# c4-tracker.net
KiCad netlist of a schematic drawn in EAGLE
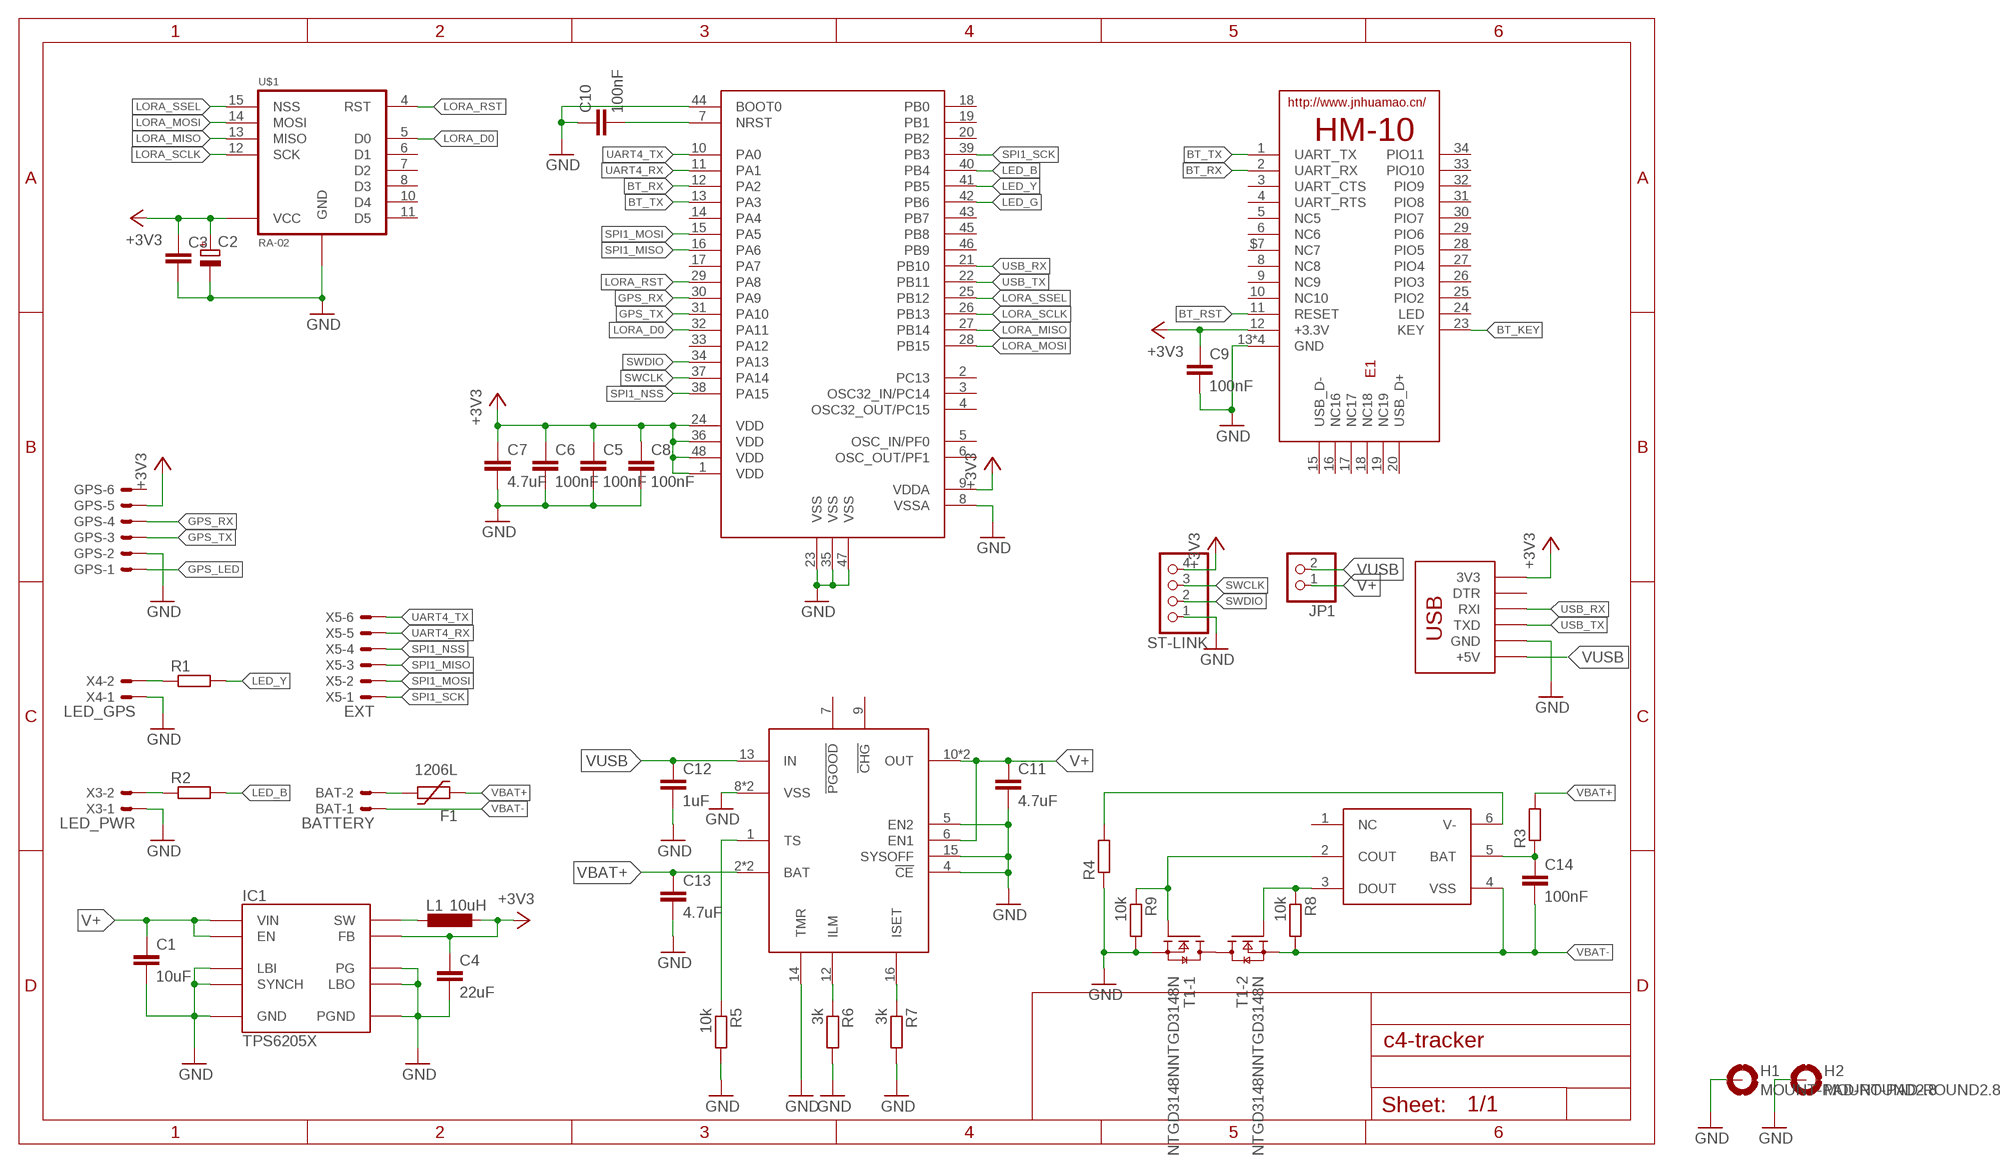
[diagram p0: schematic, sheet 1]

(export (version "E")
  (design (tool "Eeschema 10.0.6"))
  (components
    (comp (ref "BAT")
      (value "BATTERY")
      (footprint "eagle-import:53261-02")
      (libsource (lib "eagle-import") (part "53?-02261"))
    )
    (comp (ref "C1")
      (value "10uF")
      (footprint "eagle-import:C0805")
      (libsource (lib "eagle-import") (part "C-EUC0805"))
    )
    (comp (ref "C2")
      (value "CPOL-EUC")
      (footprint "eagle-import:PANASONIC_C")
      (libsource (lib "eagle-import") (part "CPOL-EUC"))
    )
    (comp (ref "C3")
      (value "C-EUC0805")
      (footprint "eagle-import:C0805")
      (libsource (lib "eagle-import") (part "C-EUC0805"))
    )
    (comp (ref "C4")
      (value "22uF")
      (footprint "eagle-import:C0805")
      (libsource (lib "eagle-import") (part "C-EUC0805"))
    )
    (comp (ref "C5")
      (value "100nF")
      (footprint "eagle-import:C0805")
      (libsource (lib "eagle-import") (part "C-EUC0805"))
    )
    (comp (ref "C6")
      (value "100nF")
      (footprint "eagle-import:C0805")
      (libsource (lib "eagle-import") (part "C-EUC0805"))
    )
    (comp (ref "C7")
      (value "4.7uF")
      (footprint "eagle-import:C0805")
      (libsource (lib "eagle-import") (part "C-EUC0805"))
    )
    (comp (ref "C8")
      (value "100nF")
      (footprint "eagle-import:C0805")
      (libsource (lib "eagle-import") (part "C-EUC0805"))
    )
    (comp (ref "C9")
      (value "100nF")
      (footprint "eagle-import:C0805")
      (libsource (lib "eagle-import") (part "C-EUC0805"))
    )
    (comp (ref "C10")
      (value "100nF")
      (footprint "eagle-import:C0805")
      (libsource (lib "eagle-import") (part "C-EUC0805"))
    )
    (comp (ref "C11")
      (value "4.7uF")
      (footprint "eagle-import:C0805")
      (libsource (lib "eagle-import") (part "C-EUC0805"))
    )
    (comp (ref "C12")
      (value "1uF")
      (footprint "eagle-import:C0805")
      (libsource (lib "eagle-import") (part "C-EUC0805"))
    )
    (comp (ref "C13")
      (value "4.7uF")
      (footprint "eagle-import:C0805")
      (libsource (lib "eagle-import") (part "C-EUC0805"))
    )
    (comp (ref "C14")
      (value "100nF")
      (footprint "eagle-import:C0805")
      (libsource (lib "eagle-import") (part "C-EUC0805"))
    )
    (comp (ref "E1")
      (value "HM-10-BOARD")
      (footprint "eagle-import:26.9X13X2.2_BOARD")
      (libsource (lib "eagle-import") (part "HM-10-BOARD"))
    )
    (comp (ref "F1")
      (value "1206L")
      (footprint "eagle-import:1206L")
      (libsource (lib "eagle-import") (part "1206L"))
    )
    (comp (ref "GPS")
      (value "53398-06")
      (footprint "eagle-import:53398-06")
      (libsource (lib "eagle-import") (part "53?-06398"))
    )
    (comp (ref "H1")
      (value "MOUNT-PAD-ROUND2.8")
      (footprint "eagle-import:2,8-PAD")
      (libsource (lib "eagle-import") (part "MOUNT-PAD-ROUND2.8"))
    )
    (comp (ref "H2")
      (value "MOUNT-PAD-ROUND2.8")
      (footprint "eagle-import:2,8-PAD")
      (libsource (lib "eagle-import") (part "MOUNT-PAD-ROUND2.8"))
    )
    (comp (ref "IC1")
      (value "TPS6205X")
      (footprint "eagle-import:VSSOP10")
      (libsource (lib "eagle-import") (part "TPS6205X"))
    )
    (comp (ref "IC2")
      (value "BQ24075/9T")
      (footprint "eagle-import:VQFN16")
      (libsource (lib "eagle-import") (part "BQ24075/9T"))
    )
    (comp (ref "JP1")
      (value "PINHD-1X2")
      (footprint "eagle-import:1X02")
      (libsource (lib "eagle-import") (part "PINHD-1X2"))
    )
    (comp (ref "L1")
      (value "10uH")
      (footprint "eagle-import:CDRH5D28R")
      (libsource (lib "eagle-import") (part "CDRH5D28R"))
    )
    (comp (ref "MC1")
      (value "STM32F030CC-48")
      (footprint "eagle-import:LQFP48-7X7")
      (libsource (lib "eagle-import") (part "STM32F030CC-48"))
    )
    (comp (ref "R1")
      (value "R-EU_R0805")
      (footprint "eagle-import:R0805")
      (libsource (lib "eagle-import") (part "R-EU_R0805"))
    )
    (comp (ref "R2")
      (value "R-EU_R0805")
      (footprint "eagle-import:R0805")
      (libsource (lib "eagle-import") (part "R-EU_R0805"))
    )
    (comp (ref "R3")
      (value "R-EU_R0805")
      (footprint "eagle-import:R0805")
      (libsource (lib "eagle-import") (part "R-EU_R0805"))
    )
    (comp (ref "R4")
      (value "R-EU_R0805")
      (footprint "eagle-import:R0805")
      (libsource (lib "eagle-import") (part "R-EU_R0805"))
    )
    (comp (ref "R5")
      (value "10k")
      (footprint "eagle-import:R0805")
      (libsource (lib "eagle-import") (part "R-EU_R0805"))
    )
    (comp (ref "R6")
      (value "3k")
      (footprint "eagle-import:R0805")
      (libsource (lib "eagle-import") (part "R-EU_R0805"))
    )
    (comp (ref "R7")
      (value "3k")
      (footprint "eagle-import:R0805")
      (libsource (lib "eagle-import") (part "R-EU_R0805"))
    )
    (comp (ref "R8")
      (value "10k")
      (footprint "eagle-import:R0805")
      (libsource (lib "eagle-import") (part "R-EU_R0805"))
    )
    (comp (ref "R9")
      (value "10k")
      (footprint "eagle-import:R0805")
      (libsource (lib "eagle-import") (part "R-EU_R0805"))
    )
    (comp (ref "ST-LINK")
      (value "PINHD-1X4")
      (footprint "eagle-import:1X04")
      (libsource (lib "eagle-import") (part "PINHD-1X4"))
    )
    (comp (ref "T1")
      (value "NTGD3148NNTGD3148N")
      (footprint "eagle-import:TSOP-6")
      (libsource (lib "eagle-import") (part "NTGD3148NNTGD3148N"))
    )
    (comp (ref "U$1")
      (value "RA-02")
      (footprint "eagle-import:RA-01_RA-02")
      (libsource (lib "eagle-import") (part "RA-02"))
    )
    (comp (ref "U$2")
      (value "RS232_USB")
      (footprint "eagle-import:CP2102_MICRO_USB_BOARD")
      (libsource (lib "eagle-import") (part "RS232_USB"))
    )
    (comp (ref "U$3")
      (value "BQ2970")
      (footprint "eagle-import:WSON6")
      (libsource (lib "eagle-import") (part "BQ2970"))
    )
    (comp (ref "X3")
      (value "LED_PWR")
      (footprint "eagle-import:53261-02")
      (libsource (lib "eagle-import") (part "53?-02261"))
    )
    (comp (ref "X4")
      (value "LED_GPS")
      (footprint "eagle-import:53261-02")
      (libsource (lib "eagle-import") (part "53?-02261"))
    )
    (comp (ref "X5")
      (value "EXT")
      (footprint "eagle-import:53261-06")
      (libsource (lib "eagle-import") (part "53?-06261"))
    )
  )
  (nets
    (net (code "1") (name "+3V3") (class "Default")
      (node (ref "C2") (pin "+") (pinfunction "+_+") (pintype "passive"))
      (node (ref "C3") (pin "1") (pinfunction "1_1") (pintype "passive"))
      (node (ref "C4") (pin "1") (pinfunction "1_1") (pintype "passive"))
      (node (ref "C5") (pin "1") (pinfunction "1_1") (pintype "passive"))
      (node (ref "C6") (pin "1") (pinfunction "1_1") (pintype "passive"))
      (node (ref "C7") (pin "1") (pinfunction "1_1") (pintype "passive"))
      (node (ref "C8") (pin "1") (pinfunction "1_1") (pintype "passive"))
      (node (ref "C9") (pin "1") (pinfunction "1_1") (pintype "passive"))
      (node (ref "E1") (pin "12") (pinfunction "+3.3V_12") (pintype "bidirectional"))
      (node (ref "GPS") (pin "5") (pinfunction "S_5") (pintype "passive"))
      (node (ref "IC1") (pin "P$5") (pinfunction "FB_P$5") (pintype "bidirectional"))
      (node (ref "L1") (pin "1") (pinfunction "1_1") (pintype "passive"))
      (node (ref "MC1") (pin "1") (pinfunction "VDD_1") (pintype "bidirectional"))
      (node (ref "MC1") (pin "24") (pinfunction "VDD_24") (pintype "bidirectional"))
      (node (ref "MC1") (pin "36") (pinfunction "VDD_36") (pintype "bidirectional"))
      (node (ref "MC1") (pin "48") (pinfunction "VDD_48") (pintype "bidirectional"))
      (node (ref "MC1") (pin "9") (pinfunction "VDDA_9") (pintype "bidirectional"))
      (node (ref "ST-LINK") (pin "4") (pinfunction "4_4") (pintype "passive"))
      (node (ref "U$1") (pin "3") (pinfunction "VCC_3") (pintype "power_in"))
      (node (ref "U$2") (pin "3V3") (pinfunction "3V3_3V3") (pintype "power_in"))
    )
    (net (code "2") (name "BT_KEY") (class "Default")
      (node (ref "E1") (pin "23") (pinfunction "KEY_23") (pintype "bidirectional"))
    )
    (net (code "3") (name "BT_RST") (class "Default")
      (node (ref "E1") (pin "11") (pinfunction "RESET_11") (pintype "bidirectional"))
    )
    (net (code "4") (name "BT_RX") (class "Default")
      (node (ref "E1") (pin "2") (pinfunction "UART_RX_2") (pintype "bidirectional"))
      (node (ref "MC1") (pin "12") (pinfunction "PA2_12") (pintype "bidirectional"))
    )
    (net (code "5") (name "BT_TX") (class "Default")
      (node (ref "E1") (pin "1") (pinfunction "UART_TX_1") (pintype "bidirectional"))
      (node (ref "MC1") (pin "13") (pinfunction "PA3_13") (pintype "bidirectional"))
    )
    (net (code "6") (name "GND") (class "Default")
      (node (ref "C1") (pin "2") (pinfunction "2_2") (pintype "passive"))
      (node (ref "C10") (pin "1") (pinfunction "1_1") (pintype "passive"))
      (node (ref "C11") (pin "2") (pinfunction "2_2") (pintype "passive"))
      (node (ref "C12") (pin "2") (pinfunction "2_2") (pintype "passive"))
      (node (ref "C13") (pin "2") (pinfunction "2_2") (pintype "passive"))
      (node (ref "C2") (pin "-") (pinfunction "-_-") (pintype "passive"))
      (node (ref "C3") (pin "2") (pinfunction "2_2") (pintype "passive"))
      (node (ref "C4") (pin "2") (pinfunction "2_2") (pintype "passive"))
      (node (ref "C5") (pin "2") (pinfunction "2_2") (pintype "passive"))
      (node (ref "C6") (pin "2") (pinfunction "2_2") (pintype "passive"))
      (node (ref "C7") (pin "2") (pinfunction "2_2") (pintype "passive"))
      (node (ref "C8") (pin "2") (pinfunction "2_2") (pintype "passive"))
      (node (ref "C9") (pin "2") (pinfunction "2_2") (pintype "passive"))
      (node (ref "E1") (pin "13") (pinfunction "GND_13") (pintype "bidirectional"))
      (node (ref "E1") (pin "14") (pinfunction "GND_14") (pintype "bidirectional"))
      (node (ref "E1") (pin "21") (pinfunction "GND_21") (pintype "bidirectional"))
      (node (ref "E1") (pin "22") (pinfunction "GND_22") (pintype "bidirectional"))
      (node (ref "GPS") (pin "2") (pinfunction "S_2") (pintype "passive"))
      (node (ref "H1") (pin "B2,8") (pinfunction "MOUNT_B2,8") (pintype "passive"))
      (node (ref "H2") (pin "B2,8") (pinfunction "MOUNT_B2,8") (pintype "passive"))
      (node (ref "IC1") (pin "P$10") (pinfunction "PGND_P$10") (pintype "bidirectional"))
      (node (ref "IC1") (pin "P$2") (pinfunction "LBO_P$2") (pintype "bidirectional"))
      (node (ref "IC1") (pin "P$3") (pinfunction "GND_P$3") (pintype "power_in"))
      (node (ref "IC1") (pin "P$4") (pinfunction "PG_P$4") (pintype "bidirectional"))
      (node (ref "IC1") (pin "P$6") (pinfunction "LBI_P$6") (pintype "bidirectional"))
      (node (ref "IC1") (pin "P$7") (pinfunction "SYNCH_P$7") (pintype "bidirectional"))
      (node (ref "IC2") (pin "14") (pinfunction "TMR_14") (pintype "bidirectional"))
      (node (ref "IC2") (pin "15") (pinfunction "SYSOFF_15") (pintype "bidirectional"))
      (node (ref "IC2") (pin "17") (pinfunction "VSS_17") (pintype "bidirectional"))
      (node (ref "IC2") (pin "4") (pinfunction "~{CE}_4") (pintype "bidirectional"))
      (node (ref "IC2") (pin "5") (pinfunction "EN2_5") (pintype "bidirectional"))
      (node (ref "IC2") (pin "8") (pinfunction "VSS_8") (pintype "bidirectional"))
      (node (ref "MC1") (pin "23") (pinfunction "VSS_23") (pintype "bidirectional"))
      (node (ref "MC1") (pin "35") (pinfunction "VSS_35") (pintype "bidirectional"))
      (node (ref "MC1") (pin "44") (pinfunction "BOOT0_44") (pintype "bidirectional"))
      (node (ref "MC1") (pin "47") (pinfunction "VSS_47") (pintype "bidirectional"))
      (node (ref "MC1") (pin "8") (pinfunction "VSSA_8") (pintype "bidirectional"))
      (node (ref "R4") (pin "1") (pinfunction "1_1") (pintype "passive"))
      (node (ref "R5") (pin "2") (pinfunction "2_2") (pintype "passive"))
      (node (ref "R6") (pin "2") (pinfunction "2_2") (pintype "passive"))
      (node (ref "R7") (pin "2") (pinfunction "2_2") (pintype "passive"))
      (node (ref "R9") (pin "2") (pinfunction "2_2") (pintype "passive"))
      (node (ref "ST-LINK") (pin "1") (pinfunction "1_1") (pintype "passive"))
      (node (ref "T1") (pin "5") (pinfunction "S_5") (pintype "passive"))
      (node (ref "U$1") (pin "1") (pinfunction "GND_1") (pintype "power_in"))
      (node (ref "U$1") (pin "16") (pinfunction "GND_16") (pintype "power_in"))
      (node (ref "U$1") (pin "2") (pinfunction "GND_2") (pintype "power_in"))
      (node (ref "U$1") (pin "9") (pinfunction "GND_9") (pintype "power_in"))
      (node (ref "U$2") (pin "GND") (pinfunction "GND_GND") (pintype "power_in"))
      (node (ref "X3") (pin "1") (pinfunction "S_1") (pintype "passive"))
      (node (ref "X4") (pin "1") (pinfunction "S_1") (pintype "passive"))
    )
    (net (code "7") (name "GPS_LED") (class "Default")
      (node (ref "GPS") (pin "1") (pinfunction "S_1") (pintype "passive"))
    )
    (net (code "8") (name "GPS_RX") (class "Default")
      (node (ref "GPS") (pin "4") (pinfunction "S_4") (pintype "passive"))
      (node (ref "MC1") (pin "30") (pinfunction "PA9_30") (pintype "bidirectional"))
    )
    (net (code "9") (name "GPS_TX") (class "Default")
      (node (ref "GPS") (pin "3") (pinfunction "S_3") (pintype "passive"))
      (node (ref "MC1") (pin "31") (pinfunction "PA10_31") (pintype "bidirectional"))
    )
    (net (code "10") (name "LED_B") (class "Default")
      (node (ref "MC1") (pin "40") (pinfunction "PB4_40") (pintype "bidirectional"))
      (node (ref "R2") (pin "2") (pinfunction "2_2") (pintype "passive"))
    )
    (net (code "11") (name "LED_G") (class "Default")
      (node (ref "MC1") (pin "42") (pinfunction "PB6_42") (pintype "bidirectional"))
    )
    (net (code "12") (name "LED_Y") (class "Default")
      (node (ref "MC1") (pin "41") (pinfunction "PB5_41") (pintype "bidirectional"))
      (node (ref "R1") (pin "2") (pinfunction "2_2") (pintype "passive"))
    )
    (net (code "13") (name "LORA_D0") (class "Default")
      (node (ref "MC1") (pin "32") (pinfunction "PA11_32") (pintype "bidirectional"))
      (node (ref "U$1") (pin "5") (pinfunction "D0_5") (pintype "bidirectional"))
    )
    (net (code "14") (name "LORA_MISO") (class "Default")
      (node (ref "MC1") (pin "27") (pinfunction "PB14_27") (pintype "bidirectional"))
      (node (ref "U$1") (pin "13") (pinfunction "MISO_13") (pintype "bidirectional"))
    )
    (net (code "15") (name "LORA_MOSI") (class "Default")
      (node (ref "MC1") (pin "28") (pinfunction "PB15_28") (pintype "bidirectional"))
      (node (ref "U$1") (pin "14") (pinfunction "MOSI_14") (pintype "bidirectional"))
    )
    (net (code "16") (name "LORA_RST") (class "Default")
      (node (ref "MC1") (pin "29") (pinfunction "PA8_29") (pintype "bidirectional"))
      (node (ref "U$1") (pin "4") (pinfunction "RST_4") (pintype "bidirectional"))
    )
    (net (code "17") (name "LORA_SCLK") (class "Default")
      (node (ref "MC1") (pin "26") (pinfunction "PB13_26") (pintype "bidirectional"))
      (node (ref "U$1") (pin "12") (pinfunction "SCK_12") (pintype "bidirectional"))
    )
    (net (code "18") (name "LORA_SSEL") (class "Default")
      (node (ref "MC1") (pin "25") (pinfunction "PB12_25") (pintype "bidirectional"))
      (node (ref "U$1") (pin "15") (pinfunction "NSS_15") (pintype "bidirectional"))
    )
    (net (code "19") (name "Net-(BATB-S)") (class "Default")
      (node (ref "BAT") (pin "2") (pinfunction "S_2") (pintype "passive"))
      (node (ref "F1") (pin "P$2") (pinfunction "2_P$2") (pintype "passive"))
    )
    (net (code "20") (name "Net-(IC1-SW)") (class "Default")
      (node (ref "IC1") (pin "P$9") (pinfunction "SW_P$9") (pintype "bidirectional"))
      (node (ref "L1") (pin "2") (pinfunction "2_2") (pintype "passive"))
    )
    (net (code "21") (name "Net-(IC2-ILM)") (class "Default")
      (node (ref "IC2") (pin "12") (pinfunction "ILM_12") (pintype "bidirectional"))
      (node (ref "R6") (pin "1") (pinfunction "1_1") (pintype "passive"))
    )
    (net (code "22") (name "Net-(IC2-ISET)") (class "Default")
      (node (ref "IC2") (pin "16") (pinfunction "ISET_16") (pintype "bidirectional"))
      (node (ref "R7") (pin "1") (pinfunction "1_1") (pintype "passive"))
    )
    (net (code "23") (name "Net-(IC2-TS)") (class "Default")
      (node (ref "IC2") (pin "1") (pinfunction "TS_1") (pintype "bidirectional"))
      (node (ref "R5") (pin "1") (pinfunction "1_1") (pintype "passive"))
    )
    (net (code "24") (name "Net-(MC1-NRST)") (class "Default")
      (node (ref "C10") (pin "2") (pinfunction "2_2") (pintype "passive"))
      (node (ref "MC1") (pin "7") (pinfunction "NRST_7") (pintype "bidirectional"))
    )
    (net (code "25") (name "Net-(T1A-D)") (class "Default")
      (node (ref "T1") (pin "4") (pinfunction "D_4") (pintype "passive"))
      (node (ref "T1") (pin "6") (pinfunction "D_6") (pintype "passive"))
    )
    (net (code "26") (name "Net-(T1A-G)") (class "Default")
      (node (ref "R9") (pin "1") (pinfunction "1_1") (pintype "passive"))
      (node (ref "T1") (pin "1") (pinfunction "G_1") (pintype "passive"))
      (node (ref "U$3") (pin "2") (pinfunction "COUT_2") (pintype "bidirectional"))
    )
    (net (code "27") (name "Net-(T1B-G)") (class "Default")
      (node (ref "R8") (pin "1") (pinfunction "1_1") (pintype "passive"))
      (node (ref "T1") (pin "3") (pinfunction "G_3") (pintype "passive"))
      (node (ref "U$3") (pin "3") (pinfunction "DOUT_3") (pintype "bidirectional"))
    )
    (net (code "28") (name "Net-(U$3-BAT)") (class "Default")
      (node (ref "C14") (pin "1") (pinfunction "1_1") (pintype "passive"))
      (node (ref "R3") (pin "1") (pinfunction "1_1") (pintype "passive"))
      (node (ref "U$3") (pin "5") (pinfunction "BAT_5") (pintype "bidirectional"))
    )
    (net (code "29") (name "Net-(U$3-V-)") (class "Default")
      (node (ref "R4") (pin "2") (pinfunction "2_2") (pintype "passive"))
      (node (ref "U$3") (pin "6") (pinfunction "V-_6") (pintype "bidirectional"))
    )
    (net (code "30") (name "Net-(X3B-S)") (class "Default")
      (node (ref "R2") (pin "1") (pinfunction "1_1") (pintype "passive"))
      (node (ref "X3") (pin "2") (pinfunction "S_2") (pintype "passive"))
    )
    (net (code "31") (name "Net-(X4B-S)") (class "Default")
      (node (ref "R1") (pin "1") (pinfunction "1_1") (pintype "passive"))
      (node (ref "X4") (pin "2") (pinfunction "S_2") (pintype "passive"))
    )
    (net (code "32") (name "SPI1_MISO") (class "Default")
      (node (ref "MC1") (pin "16") (pinfunction "PA6_16") (pintype "bidirectional"))
      (node (ref "X5") (pin "3") (pinfunction "S_3") (pintype "passive"))
    )
    (net (code "33") (name "SPI1_MOSI") (class "Default")
      (node (ref "MC1") (pin "15") (pinfunction "PA5_15") (pintype "bidirectional"))
      (node (ref "X5") (pin "2") (pinfunction "S_2") (pintype "passive"))
    )
    (net (code "34") (name "SPI1_NSS") (class "Default")
      (node (ref "MC1") (pin "38") (pinfunction "PA15_38") (pintype "bidirectional"))
      (node (ref "X5") (pin "4") (pinfunction "S_4") (pintype "passive"))
    )
    (net (code "35") (name "SPI1_SCK") (class "Default")
      (node (ref "MC1") (pin "39") (pinfunction "PB3_39") (pintype "bidirectional"))
      (node (ref "X5") (pin "1") (pinfunction "S_1") (pintype "passive"))
    )
    (net (code "36") (name "SWCLK") (class "Default")
      (node (ref "MC1") (pin "37") (pinfunction "PA14_37") (pintype "bidirectional"))
      (node (ref "ST-LINK") (pin "3") (pinfunction "3_3") (pintype "passive"))
    )
    (net (code "37") (name "SWDIO") (class "Default")
      (node (ref "MC1") (pin "34") (pinfunction "PA13_34") (pintype "bidirectional"))
      (node (ref "ST-LINK") (pin "2") (pinfunction "2_2") (pintype "passive"))
    )
    (net (code "38") (name "UART4_RX") (class "Default")
      (node (ref "MC1") (pin "11") (pinfunction "PA1_11") (pintype "bidirectional"))
      (node (ref "X5") (pin "5") (pinfunction "S_5") (pintype "passive"))
    )
    (net (code "39") (name "UART4_TX") (class "Default")
      (node (ref "MC1") (pin "10") (pinfunction "PA0_10") (pintype "bidirectional"))
      (node (ref "X5") (pin "6") (pinfunction "S_6") (pintype "passive"))
    )
    (net (code "40") (name "USB_RX") (class "Default")
      (node (ref "MC1") (pin "21") (pinfunction "PB10_21") (pintype "bidirectional"))
      (node (ref "U$2") (pin "RXI") (pinfunction "RXI_RXI") (pintype "input"))
    )
    (net (code "41") (name "USB_TX") (class "Default")
      (node (ref "MC1") (pin "22") (pinfunction "PB11_22") (pintype "bidirectional"))
      (node (ref "U$2") (pin "TXD") (pinfunction "TXD_TXD") (pintype "output"))
    )
    (net (code "42") (name "V+") (class "Default")
      (node (ref "C1") (pin "1") (pinfunction "1_1") (pintype "passive"))
      (node (ref "C11") (pin "1") (pinfunction "1_1") (pintype "passive"))
      (node (ref "IC1") (pin "P$1") (pinfunction "VIN_P$1") (pintype "power_in"))
      (node (ref "IC1") (pin "P$8") (pinfunction "EN_P$8") (pintype "input"))
      (node (ref "IC2") (pin "10") (pinfunction "OUT_10") (pintype "bidirectional"))
      (node (ref "IC2") (pin "11") (pinfunction "OUT_11") (pintype "bidirectional"))
      (node (ref "IC2") (pin "6") (pinfunction "EN1_6") (pintype "bidirectional"))
      (node (ref "JP1") (pin "1") (pinfunction "1_1") (pintype "passive"))
    )
    (net (code "43") (name "VBAT+") (class "Default")
      (node (ref "C13") (pin "1") (pinfunction "1_1") (pintype "passive"))
      (node (ref "F1") (pin "P$1") (pinfunction "1_P$1") (pintype "passive"))
      (node (ref "IC2") (pin "2") (pinfunction "BAT_2") (pintype "bidirectional"))
      (node (ref "IC2") (pin "3") (pinfunction "BAT_3") (pintype "bidirectional"))
      (node (ref "R3") (pin "2") (pinfunction "2_2") (pintype "passive"))
    )
    (net (code "44") (name "VBAT-") (class "Default")
      (node (ref "BAT") (pin "1") (pinfunction "S_1") (pintype "passive"))
      (node (ref "C14") (pin "2") (pinfunction "2_2") (pintype "passive"))
      (node (ref "R8") (pin "2") (pinfunction "2_2") (pintype "passive"))
      (node (ref "T1") (pin "2") (pinfunction "S_2") (pintype "passive"))
      (node (ref "U$3") (pin "4") (pinfunction "VSS_4") (pintype "bidirectional"))
    )
    (net (code "45") (name "VUSB") (class "Default")
      (node (ref "C12") (pin "1") (pinfunction "1_1") (pintype "passive"))
      (node (ref "IC2") (pin "13") (pinfunction "IN_13") (pintype "bidirectional"))
      (node (ref "JP1") (pin "2") (pinfunction "2_2") (pintype "passive"))
      (node (ref "U$2") (pin "+5V") (pinfunction "+5V_+5V") (pintype "power_in"))
    )
    (net (code "46") (name "unconnected-(E1-LED-Pad24)") (class "Default")
      (node (ref "E1") (pin "24") (pinfunction "LED_24") (pintype "bidirectional"))
    )
    (net (code "47") (name "unconnected-(E1-NC5-Pad5)") (class "Default")
      (node (ref "E1") (pin "5") (pinfunction "NC5_5") (pintype "bidirectional"))
    )
    (net (code "48") (name "unconnected-(E1-NC6-Pad6)") (class "Default")
      (node (ref "E1") (pin "6") (pinfunction "NC6_6") (pintype "bidirectional"))
    )
    (net (code "49") (name "unconnected-(E1-NC7-Pad$7)") (class "Default")
      (node (ref "E1") (pin "$7") (pinfunction "NC7_$7") (pintype "bidirectional"))
    )
    (net (code "50") (name "unconnected-(E1-NC8-Pad8)") (class "Default")
      (node (ref "E1") (pin "8") (pinfunction "NC8_8") (pintype "bidirectional"))
    )
    (net (code "51") (name "unconnected-(E1-NC9-Pad9)") (class "Default")
      (node (ref "E1") (pin "9") (pinfunction "NC9_9") (pintype "bidirectional"))
    )
    (net (code "52") (name "unconnected-(E1-NC10-Pad10)") (class "Default")
      (node (ref "E1") (pin "10") (pinfunction "NC10_10") (pintype "bidirectional"))
    )
    (net (code "53") (name "unconnected-(E1-NC16-Pad16)") (class "Default")
      (node (ref "E1") (pin "16") (pinfunction "NC16_16") (pintype "bidirectional"))
    )
    (net (code "54") (name "unconnected-(E1-NC17-Pad17)") (class "Default")
      (node (ref "E1") (pin "17") (pinfunction "NC17_17") (pintype "bidirectional"))
    )
    (net (code "55") (name "unconnected-(E1-NC18-Pad18)") (class "Default")
      (node (ref "E1") (pin "18") (pinfunction "NC18_18") (pintype "bidirectional"))
    )
    (net (code "56") (name "unconnected-(E1-NC19-Pad19)") (class "Default")
      (node (ref "E1") (pin "19") (pinfunction "NC19_19") (pintype "bidirectional"))
    )
    (net (code "57") (name "unconnected-(E1-PIO2-Pad25)") (class "Default")
      (node (ref "E1") (pin "25") (pinfunction "PIO2_25") (pintype "bidirectional"))
    )
    (net (code "58") (name "unconnected-(E1-PIO3-Pad26)") (class "Default")
      (node (ref "E1") (pin "26") (pinfunction "PIO3_26") (pintype "bidirectional"))
    )
    (net (code "59") (name "unconnected-(E1-PIO4-Pad27)") (class "Default")
      (node (ref "E1") (pin "27") (pinfunction "PIO4_27") (pintype "bidirectional"))
    )
    (net (code "60") (name "unconnected-(E1-PIO5-Pad28)") (class "Default")
      (node (ref "E1") (pin "28") (pinfunction "PIO5_28") (pintype "bidirectional"))
    )
    (net (code "61") (name "unconnected-(E1-PIO6-Pad29)") (class "Default")
      (node (ref "E1") (pin "29") (pinfunction "PIO6_29") (pintype "bidirectional"))
    )
    (net (code "62") (name "unconnected-(E1-PIO7-Pad30)") (class "Default")
      (node (ref "E1") (pin "30") (pinfunction "PIO7_30") (pintype "bidirectional"))
    )
    (net (code "63") (name "unconnected-(E1-PIO8-Pad31)") (class "Default")
      (node (ref "E1") (pin "31") (pinfunction "PIO8_31") (pintype "bidirectional"))
    )
    (net (code "64") (name "unconnected-(E1-PIO9-Pad32)") (class "Default")
      (node (ref "E1") (pin "32") (pinfunction "PIO9_32") (pintype "bidirectional"))
    )
    (net (code "65") (name "unconnected-(E1-PIO10-Pad33)") (class "Default")
      (node (ref "E1") (pin "33") (pinfunction "PIO10_33") (pintype "bidirectional"))
    )
    (net (code "66") (name "unconnected-(E1-PIO11-Pad34)") (class "Default")
      (node (ref "E1") (pin "34") (pinfunction "PIO11_34") (pintype "bidirectional"))
    )
    (net (code "67") (name "unconnected-(E1-UART_CTS-Pad3)") (class "Default")
      (node (ref "E1") (pin "3") (pinfunction "UART_CTS_3") (pintype "bidirectional"))
    )
    (net (code "68") (name "unconnected-(E1-UART_RTS-Pad4)") (class "Default")
      (node (ref "E1") (pin "4") (pinfunction "UART_RTS_4") (pintype "bidirectional"))
    )
    (net (code "69") (name "unconnected-(E1-USB_D+-Pad20)") (class "Default")
      (node (ref "E1") (pin "20") (pinfunction "USB_D+_20") (pintype "bidirectional"))
    )
    (net (code "70") (name "unconnected-(E1-USB_D--Pad15)") (class "Default")
      (node (ref "E1") (pin "15") (pinfunction "USB_D-_15") (pintype "bidirectional"))
    )
    (net (code "71") (name "unconnected-(GPSF-S-Pad6)") (class "Default")
      (node (ref "GPS") (pin "6") (pinfunction "S_6") (pintype "passive"))
    )
    (net (code "72") (name "unconnected-(IC2-~{CHG}-Pad9)") (class "Default")
      (node (ref "IC2") (pin "9") (pinfunction "~{CHG}_9") (pintype "bidirectional"))
    )
    (net (code "73") (name "unconnected-(IC2-~{PGOOD}-Pad7)") (class "Default")
      (node (ref "IC2") (pin "7") (pinfunction "~{PGOOD}_7") (pintype "bidirectional"))
    )
    (net (code "74") (name "unconnected-(MC1-OSC32_IN{slash}PC14-Pad3)") (class "Default")
      (node (ref "MC1") (pin "3") (pinfunction "OSC32_IN/PC14_3") (pintype "bidirectional"))
    )
    (net (code "75") (name "unconnected-(MC1-OSC32_OUT{slash}PC15-Pad4)") (class "Default")
      (node (ref "MC1") (pin "4") (pinfunction "OSC32_OUT/PC15_4") (pintype "bidirectional"))
    )
    (net (code "76") (name "unconnected-(MC1-OSC_IN{slash}PF0-Pad5)") (class "Default")
      (node (ref "MC1") (pin "5") (pinfunction "OSC_IN/PF0_5") (pintype "bidirectional"))
    )
    (net (code "77") (name "unconnected-(MC1-OSC_OUT{slash}PF1-Pad6)") (class "Default")
      (node (ref "MC1") (pin "6") (pinfunction "OSC_OUT/PF1_6") (pintype "bidirectional"))
    )
    (net (code "78") (name "unconnected-(MC1-PA4-Pad14)") (class "Default")
      (node (ref "MC1") (pin "14") (pinfunction "PA4_14") (pintype "bidirectional"))
    )
    (net (code "79") (name "unconnected-(MC1-PA7-Pad17)") (class "Default")
      (node (ref "MC1") (pin "17") (pinfunction "PA7_17") (pintype "bidirectional"))
    )
    (net (code "80") (name "unconnected-(MC1-PA12-Pad33)") (class "Default")
      (node (ref "MC1") (pin "33") (pinfunction "PA12_33") (pintype "bidirectional"))
    )
    (net (code "81") (name "unconnected-(MC1-PB0-Pad18)") (class "Default")
      (node (ref "MC1") (pin "18") (pinfunction "PB0_18") (pintype "bidirectional"))
    )
    (net (code "82") (name "unconnected-(MC1-PB1-Pad19)") (class "Default")
      (node (ref "MC1") (pin "19") (pinfunction "PB1_19") (pintype "bidirectional"))
    )
    (net (code "83") (name "unconnected-(MC1-PB2-Pad20)") (class "Default")
      (node (ref "MC1") (pin "20") (pinfunction "PB2_20") (pintype "bidirectional"))
    )
    (net (code "84") (name "unconnected-(MC1-PB7-Pad43)") (class "Default")
      (node (ref "MC1") (pin "43") (pinfunction "PB7_43") (pintype "bidirectional"))
    )
    (net (code "85") (name "unconnected-(MC1-PB8-Pad45)") (class "Default")
      (node (ref "MC1") (pin "45") (pinfunction "PB8_45") (pintype "bidirectional"))
    )
    (net (code "86") (name "unconnected-(MC1-PB9-Pad46)") (class "Default")
      (node (ref "MC1") (pin "46") (pinfunction "PB9_46") (pintype "bidirectional"))
    )
    (net (code "87") (name "unconnected-(MC1-PC13-Pad2)") (class "Default")
      (node (ref "MC1") (pin "2") (pinfunction "PC13_2") (pintype "bidirectional"))
    )
    (net (code "88") (name "unconnected-(U$1-D1-Pad6)") (class "Default")
      (node (ref "U$1") (pin "6") (pinfunction "D1_6") (pintype "bidirectional"))
    )
    (net (code "89") (name "unconnected-(U$1-D2-Pad7)") (class "Default")
      (node (ref "U$1") (pin "7") (pinfunction "D2_7") (pintype "bidirectional"))
    )
    (net (code "90") (name "unconnected-(U$1-D3-Pad8)") (class "Default")
      (node (ref "U$1") (pin "8") (pinfunction "D3_8") (pintype "bidirectional"))
    )
    (net (code "91") (name "unconnected-(U$1-D4-Pad10)") (class "Default")
      (node (ref "U$1") (pin "10") (pinfunction "D4_10") (pintype "bidirectional"))
    )
    (net (code "92") (name "unconnected-(U$1-D5-Pad11)") (class "Default")
      (node (ref "U$1") (pin "11") (pinfunction "D5_11") (pintype "bidirectional"))
    )
    (net (code "93") (name "unconnected-(U$2-PadDTR)") (class "Default")
      (node (ref "U$2") (pin "DTR") (pinfunction "DTR_DTR") (pintype "bidirectional"))
    )
    (net (code "94") (name "unconnected-(U$3-NC-Pad1)") (class "Default")
      (node (ref "U$3") (pin "1") (pinfunction "NC_1") (pintype "bidirectional"))
    )
  )
)
